# CoproMKII_Ethernet.net
KiCad netlist of a schematic drawn in Altium Designer
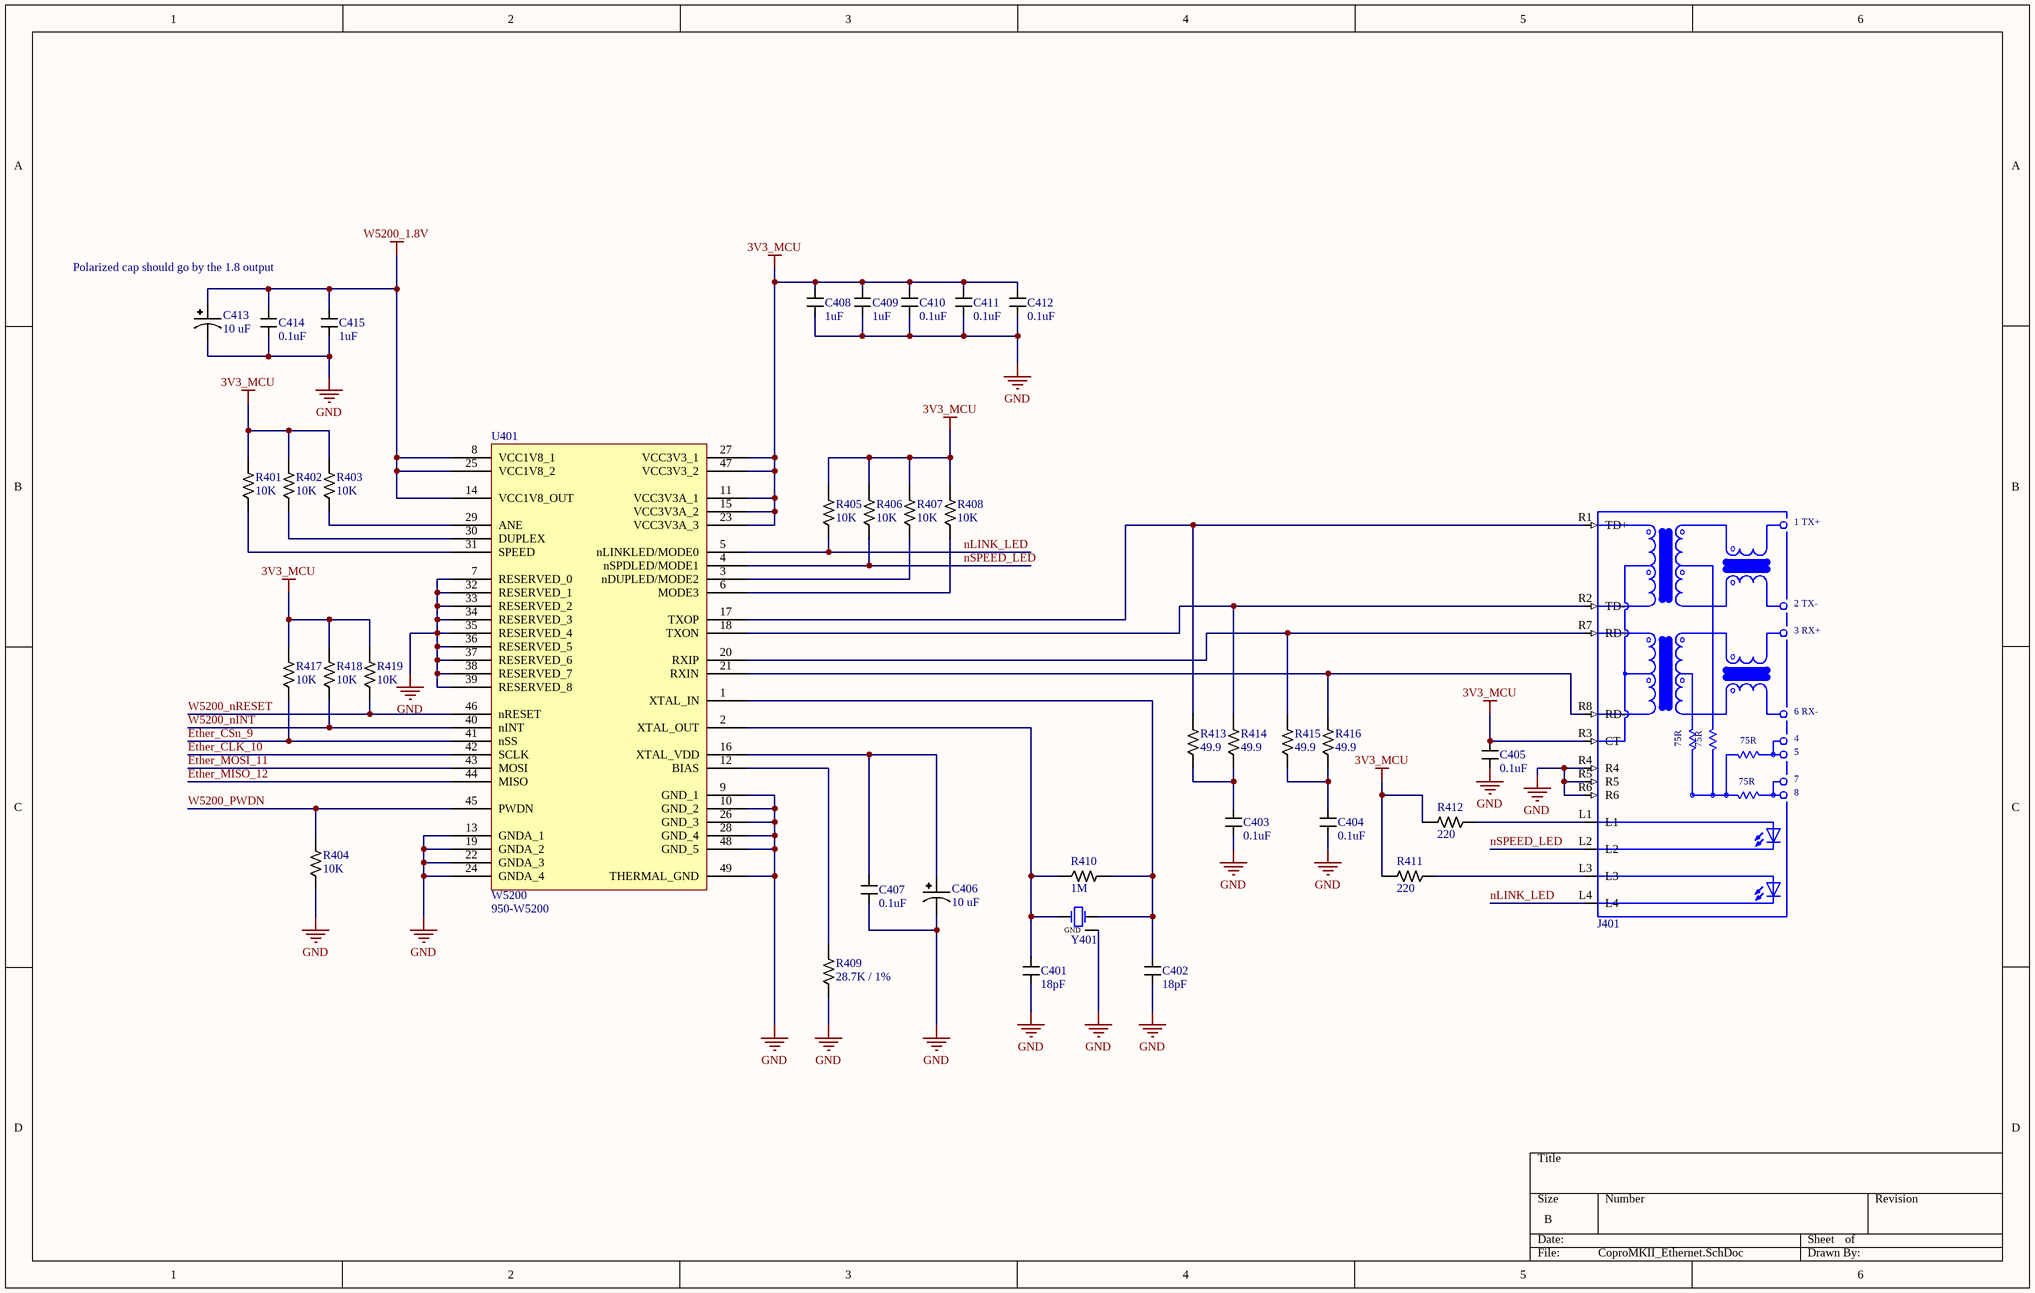
[diagram p0: CoproMKII_Ethernet.SchDoc]

(export (version "E")
  (design (tool "Eeschema 10.0.6"))
  (components
    (comp (ref "C401")
      (value "18pF")
      (footprint "CAPACITOR_0603")
      (description "Cap 18pF 50V +/-5%\r\nCeramic 0603")
      (fields
        (field (name "TOLERANCE") "+/- 5%")
        (field (name "VOLTAGE") "50V")
        (field (name "MADE BY") "Flip B")
      )
      (libsource (lib "Capacitors") (part "CAPACITOR_0.000018uF_0603"))
    )
    (comp (ref "C402")
      (value "18pF")
      (footprint "CAPACITOR_0603")
      (description "Cap 18pF 50V +/-5%\r\nCeramic 0603")
      (fields
        (field (name "TOLERANCE") "+/- 5%")
        (field (name "VOLTAGE") "50V")
        (field (name "MADE BY") "Flip B")
      )
      (libsource (lib "Capacitors") (part "CAPACITOR_0.000018uF_0603"))
    )
    (comp (ref "C403")
      (value "0.1uF")
      (footprint "CAPACITOR_0603")
      (description "Cap 100nF 6.3V +/-10%\r\nCeramic 0603")
      (fields
        (field (name "TOLERANCE") "+/- 10%")
        (field (name "VOLTAGE") "6.3V")
        (field (name "MADE BY") "Flip B")
      )
      (libsource (lib "Capacitors") (part "CAPACITOR_0.1uF_0603"))
    )
    (comp (ref "C404")
      (value "0.1uF")
      (footprint "CAPACITOR_0603")
      (description "Cap 100nF 6.3V +/-10%\r\nCeramic 0603")
      (fields
        (field (name "TOLERANCE") "+/- 10%")
        (field (name "VOLTAGE") "6.3V")
        (field (name "MADE BY") "Flip B")
      )
      (libsource (lib "Capacitors") (part "CAPACITOR_0.1uF_0603"))
    )
    (comp (ref "C405")
      (value "0.1uF")
      (footprint "CAPACITOR_0603")
      (description "Cap 100nF 6.3V +/-10%\r\nCeramic 0603")
      (fields
        (field (name "TOLERANCE") "+/- 10%")
        (field (name "VOLTAGE") "6.3V")
        (field (name "MADE BY") "Flip B")
      )
      (libsource (lib "Capacitors") (part "CAPACITOR_0.1uF_0603"))
    )
    (comp (ref "C406")
      (value "10uF Tantalum 10V")
      (footprint "CAPACITOR_0603")
      (description "Cap 10uF 10V +/-20%\r\nTantalum 0603")
      (fields
        (field (name "TOLERANCE") "+/- 20%")
        (field (name "VOLTAGE") "10V")
        (field (name "VALUE (UF)") "10 uF")
        (field (name "MADE BY") "John S")
      )
      (libsource (lib "Capacitors") (part "CAPACITOR_10uF_0603_Tantalum"))
    )
    (comp (ref "C407")
      (value "0.1uF")
      (footprint "CAPACITOR_0603")
      (description "Cap 100nF 6.3V +/-10%\r\nCeramic 0603")
      (fields
        (field (name "TOLERANCE") "+/- 10%")
        (field (name "VOLTAGE") "6.3V")
        (field (name "MADE BY") "Flip B")
      )
      (libsource (lib "Capacitors") (part "CAPACITOR_0.1uF_0603"))
    )
    (comp (ref "C408")
      (value "1uF")
      (footprint "CAPACITOR_0603")
      (description "Cap 1uF 16V +/-10%\r\nCeramic 0603")
      (fields
        (field (name "TOLERANCE") "+/- 10%")
        (field (name "VOLTAGE") "16V")
        (field (name "MADE BY") "Flip B")
      )
      (libsource (lib "Capacitors") (part "CAPACITOR_1uF_0603"))
    )
    (comp (ref "C409")
      (value "1uF")
      (footprint "CAPACITOR_0603")
      (description "Cap 1uF 16V +/-10%\r\nCeramic 0603")
      (fields
        (field (name "TOLERANCE") "+/- 10%")
        (field (name "VOLTAGE") "16V")
        (field (name "MADE BY") "Flip B")
      )
      (libsource (lib "Capacitors") (part "CAPACITOR_1uF_0603"))
    )
    (comp (ref "C410")
      (value "0.1uF")
      (footprint "CAPACITOR_0603")
      (description "Cap 100nF 6.3V +/-10%\r\nCeramic 0603")
      (fields
        (field (name "TOLERANCE") "+/- 10%")
        (field (name "VOLTAGE") "6.3V")
        (field (name "MADE BY") "Flip B")
      )
      (libsource (lib "Capacitors") (part "CAPACITOR_0.1uF_0603"))
    )
    (comp (ref "C411")
      (value "0.1uF")
      (footprint "CAPACITOR_0603")
      (description "Cap 100nF 6.3V +/-10%\r\nCeramic 0603")
      (fields
        (field (name "TOLERANCE") "+/- 10%")
        (field (name "VOLTAGE") "6.3V")
        (field (name "MADE BY") "Flip B")
      )
      (libsource (lib "Capacitors") (part "CAPACITOR_0.1uF_0603"))
    )
    (comp (ref "C412")
      (value "0.1uF")
      (footprint "CAPACITOR_0603")
      (description "Cap 100nF 6.3V +/-10%\r\nCeramic 0603")
      (fields
        (field (name "TOLERANCE") "+/- 10%")
        (field (name "VOLTAGE") "6.3V")
        (field (name "MADE BY") "Flip B")
      )
      (libsource (lib "Capacitors") (part "CAPACITOR_0.1uF_0603"))
    )
    (comp (ref "C413")
      (value "10uF Tantalum 10V")
      (footprint "CAPACITOR_0603")
      (description "Cap 10uF 10V +/-20%\r\nTantalum 0603")
      (fields
        (field (name "TOLERANCE") "+/- 20%")
        (field (name "VOLTAGE") "10V")
        (field (name "VALUE (UF)") "10 uF")
        (field (name "MADE BY") "John S")
      )
      (libsource (lib "Capacitors") (part "CAPACITOR_10uF_0603_Tantalum"))
    )
    (comp (ref "C414")
      (value "0.1uF")
      (footprint "CAPACITOR_0603")
      (description "Cap 100nF 6.3V +/-10%\r\nCeramic 0603")
      (fields
        (field (name "TOLERANCE") "+/- 10%")
        (field (name "VOLTAGE") "6.3V")
        (field (name "MADE BY") "Flip B")
      )
      (libsource (lib "Capacitors") (part "CAPACITOR_0.1uF_0603"))
    )
    (comp (ref "C415")
      (value "1uF")
      (footprint "CAPACITOR_0603")
      (description "Cap 1uF 16V +/-10%\r\nCeramic 0603")
      (fields
        (field (name "TOLERANCE") "+/- 10%")
        (field (name "VOLTAGE") "16V")
        (field (name "MADE BY") "Flip B")
      )
      (libsource (lib "Capacitors") (part "CAPACITOR_1uF_0603"))
    )
    (comp (ref "J401")
      (value "Ethernet Connector")
      (footprint "WIZNET_RB1-125BAG1A")
      (description "CONN JACK 1PORT 100 BASE-T PCB")
      (libsource (lib "Connectors") (part "RB1-125BAG1A"))
    )
    (comp (ref "R401")
      (value "10k Ohm 5% 1/10W")
      (footprint "RESISTOR_0603")
      (description "RES 10k OHM 5% 1/10W 0603")
      (fields
        (field (name "TOLERANCE") "+/- 5%")
        (field (name "VALUE  (OHMS)") "10K")
        (field (name "MADE BY") "Robert Pafford")
      )
      (libsource (lib "Resistors") (part "RESISTOR_10K_0603"))
    )
    (comp (ref "R402")
      (value "10k Ohm 5% 1/10W")
      (footprint "RESISTOR_0603")
      (description "RES 10k OHM 5% 1/10W 0603")
      (fields
        (field (name "TOLERANCE") "+/- 5%")
        (field (name "VALUE  (OHMS)") "10K")
        (field (name "MADE BY") "Robert Pafford")
      )
      (libsource (lib "Resistors") (part "RESISTOR_10K_0603"))
    )
    (comp (ref "R403")
      (value "10k Ohm 5% 1/10W")
      (footprint "RESISTOR_0603")
      (description "RES 10k OHM 5% 1/10W 0603")
      (fields
        (field (name "TOLERANCE") "+/- 5%")
        (field (name "VALUE  (OHMS)") "10K")
        (field (name "MADE BY") "Robert Pafford")
      )
      (libsource (lib "Resistors") (part "RESISTOR_10K_0603"))
    )
    (comp (ref "R404")
      (value "10k Ohm 5% 1/10W")
      (footprint "RESISTOR_0603")
      (description "RES 10k OHM 5% 1/10W 0603")
      (fields
        (field (name "TOLERANCE") "+/- 5%")
        (field (name "VALUE  (OHMS)") "10K")
        (field (name "MADE BY") "Robert Pafford")
      )
      (libsource (lib "Resistors") (part "RESISTOR_10K_0603"))
    )
    (comp (ref "R405")
      (value "10k Ohm 5% 1/10W")
      (footprint "RESISTOR_0603")
      (description "RES 10k OHM 5% 1/10W 0603")
      (fields
        (field (name "TOLERANCE") "+/- 5%")
        (field (name "VALUE  (OHMS)") "10K")
        (field (name "MADE BY") "Robert Pafford")
      )
      (libsource (lib "Resistors") (part "RESISTOR_10K_0603"))
    )
    (comp (ref "R406")
      (value "10k Ohm 5% 1/10W")
      (footprint "RESISTOR_0603")
      (description "RES 10k OHM 5% 1/10W 0603")
      (fields
        (field (name "TOLERANCE") "+/- 5%")
        (field (name "VALUE  (OHMS)") "10K")
        (field (name "MADE BY") "Robert Pafford")
      )
      (libsource (lib "Resistors") (part "RESISTOR_10K_0603"))
    )
    (comp (ref "R407")
      (value "10k Ohm 5% 1/10W")
      (footprint "RESISTOR_0603")
      (description "RES 10k OHM 5% 1/10W 0603")
      (fields
        (field (name "TOLERANCE") "+/- 5%")
        (field (name "VALUE  (OHMS)") "10K")
        (field (name "MADE BY") "Robert Pafford")
      )
      (libsource (lib "Resistors") (part "RESISTOR_10K_0603"))
    )
    (comp (ref "R408")
      (value "10k Ohm 5% 1/10W")
      (footprint "RESISTOR_0603")
      (description "RES 10k OHM 5% 1/10W 0603")
      (fields
        (field (name "TOLERANCE") "+/- 5%")
        (field (name "VALUE  (OHMS)") "10K")
        (field (name "MADE BY") "Robert Pafford")
      )
      (libsource (lib "Resistors") (part "RESISTOR_10K_0603"))
    )
    (comp (ref "R409")
      (value "K / 1%")
      (footprint "RESISTOR_0603")
      (description "RES 28.7K OHM 1% 1/8W 0603")
      (fields
        (field (name "TOLERANCE") "+/- 5%")
        (field (name "VALUE  (OHMS)") "28.7K / 1%")
        (field (name "MADE BY") "Robert Pafford")
      )
      (libsource (lib "Resistors") (part "RESISTOR_28.7K / 1%_0603"))
    )
    (comp (ref "R410")
      (value "1M")
      (footprint "RESISTOR_0603")
      (description "RES 1M OHM 1/8W 0603")
      (fields
        (field (name "TOLERANCE") "+/- 5%")
        (field (name "VALUE  (OHMS)") "1M")
        (field (name "MADE BY") "Robert Pafford")
      )
      (libsource (lib "Resistors") (part "RESISTOR_1M_0603"))
    )
    (comp (ref "R411")
      (value "220 Ohm 5% 1/8W")
      (footprint "RESISTOR_0603")
      (description "RES 220 OHM 5% 1/8W 0603")
      (fields
        (field (name "TOLERANCE") "+/- 5%")
        (field (name "VALUE  (OHMS)") "220")
        (field (name "MADE BY") "John S")
      )
      (libsource (lib "Resistors") (part "RESISTOR_200_0603"))
    )
    (comp (ref "R412")
      (value "220 Ohm 5% 1/8W")
      (footprint "RESISTOR_0603")
      (description "RES 220 OHM 5% 1/8W 0603")
      (fields
        (field (name "TOLERANCE") "+/- 5%")
        (field (name "VALUE  (OHMS)") "220")
        (field (name "MADE BY") "John S")
      )
      (libsource (lib "Resistors") (part "RESISTOR_200_0603"))
    )
    (comp (ref "R413")
      (value "49.9 Ohm 1% 1/8W")
      (footprint "RESISTOR_0603")
      (description "RES 49.9 OHM 1% 1/8W 0603")
      (fields
        (field (name "TOLERANCE") "+/- 1%")
        (field (name "VALUE  (OHMS)") "49.9")
        (field (name "MADE BY") "John S")
      )
      (libsource (lib "Resistors") (part "RESISTOR_49.9_0603"))
    )
    (comp (ref "R414")
      (value "49.9 Ohm 1% 1/8W")
      (footprint "RESISTOR_0603")
      (description "RES 49.9 OHM 1% 1/8W 0603")
      (fields
        (field (name "TOLERANCE") "+/- 1%")
        (field (name "VALUE  (OHMS)") "49.9")
        (field (name "MADE BY") "John S")
      )
      (libsource (lib "Resistors") (part "RESISTOR_49.9_0603"))
    )
    (comp (ref "R415")
      (value "49.9 Ohm 1% 1/8W")
      (footprint "RESISTOR_0603")
      (description "RES 49.9 OHM 1% 1/8W 0603")
      (fields
        (field (name "TOLERANCE") "+/- 1%")
        (field (name "VALUE  (OHMS)") "49.9")
        (field (name "MADE BY") "John S")
      )
      (libsource (lib "Resistors") (part "RESISTOR_49.9_0603"))
    )
    (comp (ref "R416")
      (value "49.9 Ohm 1% 1/8W")
      (footprint "RESISTOR_0603")
      (description "RES 49.9 OHM 1% 1/8W 0603")
      (fields
        (field (name "TOLERANCE") "+/- 1%")
        (field (name "VALUE  (OHMS)") "49.9")
        (field (name "MADE BY") "John S")
      )
      (libsource (lib "Resistors") (part "RESISTOR_49.9_0603"))
    )
    (comp (ref "R417")
      (value "10k Ohm 5% 1/10W")
      (footprint "RESISTOR_0603")
      (description "RES 10k OHM 5% 1/10W 0603")
      (fields
        (field (name "TOLERANCE") "+/- 5%")
        (field (name "VALUE  (OHMS)") "10K")
        (field (name "MADE BY") "Robert Pafford")
      )
      (libsource (lib "Resistors") (part "RESISTOR_10K_0603"))
    )
    (comp (ref "R418")
      (value "10k Ohm 5% 1/10W")
      (footprint "RESISTOR_0603")
      (description "RES 10k OHM 5% 1/10W 0603")
      (fields
        (field (name "TOLERANCE") "+/- 5%")
        (field (name "VALUE  (OHMS)") "10K")
        (field (name "MADE BY") "Robert Pafford")
      )
      (libsource (lib "Resistors") (part "RESISTOR_10K_0603"))
    )
    (comp (ref "R419")
      (value "10k Ohm 5% 1/10W")
      (footprint "RESISTOR_0603")
      (description "RES 10k OHM 5% 1/10W 0603")
      (fields
        (field (name "TOLERANCE") "+/- 5%")
        (field (name "VALUE  (OHMS)") "10K")
        (field (name "MADE BY") "Robert Pafford")
      )
      (libsource (lib "Resistors") (part "RESISTOR_10K_0603"))
    )
    (comp (ref "U401")
      (value "W5200")
      (footprint "QFN-48")
      (description "WIZNET W5200\r\n48QFN (7x7 mm)")
      (fields
        (field (name "MF") "Texas Instruments")
        (field (name "MP") "LM1117IMPX-3.3/NOPB")
        (field (name "SUPPLIER PART NUMBER 1") "950-W5200")
        (field (name "CREATED BY:") "Siddharth.V")
      )
      (libsource (lib "Integrated Circuits") (part "W5200"))
    )
    (comp (ref "Y401")
      (value "CRYSTAL 12.0000MHZ 18PF SMD")
      (footprint "4-SMD No Lead Crystal")
      (description "25 MHz ±20ppm Crystal 18pF")
      (fields (field (name "MADE BY") "Robert Pafford"))
      (libsource (lib "Crystals") (part "CRYSTAL_25MHz_SMD_1"))
    )
  )
  (nets
    (net (code "1") (name "/Ether_CLK_10") (class "Default")
      (node (ref "U401") (pin "42") (pinfunction "SCLK_42") (pintype "passive"))
    )
    (net (code "2") (name "/Ether_CSn_9") (class "Default")
      (node (ref "R417") (pin "2") (pinfunction "2_2") (pintype "passive"))
      (node (ref "U401") (pin "41") (pinfunction "nSS_41") (pintype "passive"))
    )
    (net (code "3") (name "/Ether_MISO_12") (class "Default")
      (node (ref "U401") (pin "44") (pinfunction "MISO_44") (pintype "passive"))
    )
    (net (code "4") (name "/Ether_MOSI_11") (class "Default")
      (node (ref "U401") (pin "43") (pinfunction "MOSI_43") (pintype "passive"))
    )
    (net (code "5") (name "/W5200_PWDN") (class "Default")
      (node (ref "R404") (pin "1") (pinfunction "1_1") (pintype "passive"))
      (node (ref "U401") (pin "45") (pinfunction "PWDN_45") (pintype "passive"))
    )
    (net (code "6") (name "/W5200_nINT") (class "Default")
      (node (ref "R418") (pin "2") (pinfunction "2_2") (pintype "passive"))
      (node (ref "U401") (pin "40") (pinfunction "nINT_40") (pintype "passive"))
    )
    (net (code "7") (name "/W5200_nRESET") (class "Default")
      (node (ref "R419") (pin "2") (pinfunction "2_2") (pintype "passive"))
      (node (ref "U401") (pin "46") (pinfunction "nRESET_46") (pintype "passive"))
    )
    (net (code "8") (name "/nLINK_LED") (class "Default")
      (node (ref "J401") (pin "L4") (pinfunction "L4_L4") (pintype "passive"))
      (node (ref "R405") (pin "2") (pinfunction "2_2") (pintype "passive"))
      (node (ref "U401") (pin "5") (pinfunction "nLINKLED/MODE0_5") (pintype "passive"))
    )
    (net (code "9") (name "/nSPEED_LED") (class "Default")
      (node (ref "J401") (pin "L2") (pinfunction "L2_L2") (pintype "passive"))
      (node (ref "R406") (pin "2") (pinfunction "2_2") (pintype "passive"))
      (node (ref "U401") (pin "4") (pinfunction "nSPDLED/MODE1_4") (pintype "passive"))
    )
    (net (code "10") (name "3V3_MCU") (class "Default")
      (node (ref "C405") (pin "1") (pinfunction "1_1") (pintype "passive"))
      (node (ref "C408") (pin "1") (pinfunction "1_1") (pintype "passive"))
      (node (ref "C409") (pin "1") (pinfunction "1_1") (pintype "passive"))
      (node (ref "C410") (pin "1") (pinfunction "1_1") (pintype "passive"))
      (node (ref "C411") (pin "1") (pinfunction "1_1") (pintype "passive"))
      (node (ref "C412") (pin "1") (pinfunction "1_1") (pintype "passive"))
      (node (ref "J401") (pin "R3") (pinfunction "CT_R3") (pintype "input"))
      (node (ref "R401") (pin "1") (pinfunction "1_1") (pintype "passive"))
      (node (ref "R402") (pin "1") (pinfunction "1_1") (pintype "passive"))
      (node (ref "R403") (pin "1") (pinfunction "1_1") (pintype "passive"))
      (node (ref "R405") (pin "1") (pinfunction "1_1") (pintype "passive"))
      (node (ref "R406") (pin "1") (pinfunction "1_1") (pintype "passive"))
      (node (ref "R407") (pin "1") (pinfunction "1_1") (pintype "passive"))
      (node (ref "R408") (pin "1") (pinfunction "1_1") (pintype "passive"))
      (node (ref "R411") (pin "1") (pinfunction "1_1") (pintype "passive"))
      (node (ref "R412") (pin "1") (pinfunction "1_1") (pintype "passive"))
      (node (ref "R417") (pin "1") (pinfunction "1_1") (pintype "passive"))
      (node (ref "R418") (pin "1") (pinfunction "1_1") (pintype "passive"))
      (node (ref "R419") (pin "1") (pinfunction "1_1") (pintype "passive"))
      (node (ref "U401") (pin "11") (pinfunction "VCC3V3A_1_11") (pintype "passive"))
      (node (ref "U401") (pin "15") (pinfunction "VCC3V3A_2_15") (pintype "passive"))
      (node (ref "U401") (pin "23") (pinfunction "VCC3V3A_3_23") (pintype "passive"))
      (node (ref "U401") (pin "27") (pinfunction "VCC3V3_1_27") (pintype "passive"))
      (node (ref "U401") (pin "47") (pinfunction "VCC3V3_2_47") (pintype "passive"))
    )
    (net (code "11") (name "GND") (class "Default")
      (node (ref "C401") (pin "2") (pinfunction "2_2") (pintype "passive"))
      (node (ref "C402") (pin "2") (pinfunction "2_2") (pintype "passive"))
      (node (ref "C403") (pin "2") (pinfunction "2_2") (pintype "passive"))
      (node (ref "C404") (pin "2") (pinfunction "2_2") (pintype "passive"))
      (node (ref "C405") (pin "2") (pinfunction "2_2") (pintype "passive"))
      (node (ref "C406") (pin "2") (pintype "passive"))
      (node (ref "C407") (pin "2") (pinfunction "2_2") (pintype "passive"))
      (node (ref "C408") (pin "2") (pinfunction "2_2") (pintype "passive"))
      (node (ref "C409") (pin "2") (pinfunction "2_2") (pintype "passive"))
      (node (ref "C410") (pin "2") (pinfunction "2_2") (pintype "passive"))
      (node (ref "C411") (pin "2") (pinfunction "2_2") (pintype "passive"))
      (node (ref "C412") (pin "2") (pinfunction "2_2") (pintype "passive"))
      (node (ref "C413") (pin "2") (pintype "passive"))
      (node (ref "C414") (pin "2") (pinfunction "2_2") (pintype "passive"))
      (node (ref "C415") (pin "2") (pinfunction "2_2") (pintype "passive"))
      (node (ref "J401") (pin "R4") (pinfunction "R4_R4") (pintype "input"))
      (node (ref "J401") (pin "R5") (pinfunction "R5_R5") (pintype "input"))
      (node (ref "J401") (pin "R6") (pinfunction "R6_R6") (pintype "input"))
      (node (ref "R404") (pin "2") (pinfunction "2_2") (pintype "passive"))
      (node (ref "R409") (pin "2") (pinfunction "2_2") (pintype "passive"))
      (node (ref "U401") (pin "10") (pinfunction "GND_2_10") (pintype "passive"))
      (node (ref "U401") (pin "13") (pinfunction "GNDA_1_13") (pintype "passive"))
      (node (ref "U401") (pin "19") (pinfunction "GNDA_2_19") (pintype "passive"))
      (node (ref "U401") (pin "22") (pinfunction "GNDA_3_22") (pintype "passive"))
      (node (ref "U401") (pin "24") (pinfunction "GNDA_4_24") (pintype "passive"))
      (node (ref "U401") (pin "26") (pinfunction "GND_3_26") (pintype "passive"))
      (node (ref "U401") (pin "28") (pinfunction "GND_4_28") (pintype "passive"))
      (node (ref "U401") (pin "32") (pinfunction "RESERVED_1_32") (pintype "passive"))
      (node (ref "U401") (pin "33") (pinfunction "RESERVED_2_33") (pintype "passive"))
      (node (ref "U401") (pin "34") (pinfunction "RESERVED_3_34") (pintype "passive"))
      (node (ref "U401") (pin "35") (pinfunction "RESERVED_4_35") (pintype "passive"))
      (node (ref "U401") (pin "36") (pinfunction "RESERVED_5_36") (pintype "passive"))
      (node (ref "U401") (pin "37") (pinfunction "RESERVED_6_37") (pintype "passive"))
      (node (ref "U401") (pin "38") (pinfunction "RESERVED_7_38") (pintype "passive"))
      (node (ref "U401") (pin "39") (pinfunction "RESERVED_8_39") (pintype "passive"))
      (node (ref "U401") (pin "48") (pinfunction "GND_5_48") (pintype "passive"))
      (node (ref "U401") (pin "49") (pinfunction "THERMAL_GND_49") (pintype "passive"))
      (node (ref "U401") (pin "7") (pinfunction "RESERVED_0_7") (pintype "passive"))
      (node (ref "U401") (pin "9") (pinfunction "GND_1_9") (pintype "passive"))
      (node (ref "Y401") (pin "GND") (pinfunction "GND_GND") (pintype "power_in"))
    )
    (net (code "12") (name "Net-(C403-Pad1)") (class "Default")
      (node (ref "C403") (pin "1") (pinfunction "1_1") (pintype "passive"))
      (node (ref "R413") (pin "2") (pinfunction "2_2") (pintype "passive"))
      (node (ref "R414") (pin "2") (pinfunction "2_2") (pintype "passive"))
    )
    (net (code "13") (name "Net-(C404-Pad1)") (class "Default")
      (node (ref "C404") (pin "1") (pinfunction "1_1") (pintype "passive"))
      (node (ref "R415") (pin "2") (pinfunction "2_2") (pintype "passive"))
      (node (ref "R416") (pin "2") (pinfunction "2_2") (pintype "passive"))
    )
    (net (code "14") (name "Net-(J401-PadL1)") (class "Default")
      (node (ref "J401") (pin "L1") (pinfunction "L1_L1") (pintype "passive"))
      (node (ref "R412") (pin "2") (pinfunction "2_2") (pintype "passive"))
    )
    (net (code "15") (name "Net-(J401-PadL3)") (class "Default")
      (node (ref "J401") (pin "L3") (pinfunction "L3_L3") (pintype "passive"))
      (node (ref "R411") (pin "2") (pinfunction "2_2") (pintype "passive"))
    )
    (net (code "16") (name "Net-(J401-RD+)") (class "Default")
      (node (ref "J401") (pin "R7") (pinfunction "RD+_R7") (pintype "input"))
      (node (ref "R415") (pin "1") (pinfunction "1_1") (pintype "passive"))
      (node (ref "U401") (pin "20") (pinfunction "RXIP_20") (pintype "passive"))
    )
    (net (code "17") (name "Net-(J401-RD-)") (class "Default")
      (node (ref "J401") (pin "R8") (pinfunction "RD-_R8") (pintype "input"))
      (node (ref "R416") (pin "1") (pinfunction "1_1") (pintype "passive"))
      (node (ref "U401") (pin "21") (pinfunction "RXIN_21") (pintype "passive"))
    )
    (net (code "18") (name "Net-(J401-TD+)") (class "Default")
      (node (ref "J401") (pin "R1") (pinfunction "TD+_R1") (pintype "input"))
      (node (ref "R413") (pin "1") (pinfunction "1_1") (pintype "passive"))
      (node (ref "U401") (pin "17") (pinfunction "TXOP_17") (pintype "passive"))
    )
    (net (code "19") (name "Net-(J401-TD-)") (class "Default")
      (node (ref "J401") (pin "R2") (pinfunction "TD-_R2") (pintype "input"))
      (node (ref "R414") (pin "1") (pinfunction "1_1") (pintype "passive"))
      (node (ref "U401") (pin "18") (pinfunction "TXON_18") (pintype "passive"))
    )
    (net (code "20") (name "Net-(U401-ANE)") (class "Default")
      (node (ref "R403") (pin "2") (pinfunction "2_2") (pintype "passive"))
      (node (ref "U401") (pin "29") (pinfunction "ANE_29") (pintype "passive"))
    )
    (net (code "21") (name "Net-(U401-BIAS)") (class "Default")
      (node (ref "R409") (pin "1") (pinfunction "1_1") (pintype "passive"))
      (node (ref "U401") (pin "12") (pinfunction "BIAS_12") (pintype "passive"))
    )
    (net (code "22") (name "Net-(U401-DUPLEX)") (class "Default")
      (node (ref "R402") (pin "2") (pinfunction "2_2") (pintype "passive"))
      (node (ref "U401") (pin "30") (pinfunction "DUPLEX_30") (pintype "passive"))
    )
    (net (code "23") (name "Net-(U401-MODE3)") (class "Default")
      (node (ref "R408") (pin "2") (pinfunction "2_2") (pintype "passive"))
      (node (ref "U401") (pin "6") (pinfunction "MODE3_6") (pintype "passive"))
    )
    (net (code "24") (name "Net-(U401-SPEED)") (class "Default")
      (node (ref "R401") (pin "2") (pinfunction "2_2") (pintype "passive"))
      (node (ref "U401") (pin "31") (pinfunction "SPEED_31") (pintype "passive"))
    )
    (net (code "25") (name "Net-(U401-XTAL_IN)") (class "Default")
      (node (ref "C402") (pin "1") (pinfunction "1_1") (pintype "passive"))
      (node (ref "R410") (pin "1") (pinfunction "1_1") (pintype "passive"))
      (node (ref "U401") (pin "1") (pinfunction "XTAL_IN_1") (pintype "passive"))
      (node (ref "Y401") (pin "2") (pinfunction "2_2") (pintype "passive"))
    )
    (net (code "26") (name "Net-(U401-XTAL_OUT)") (class "Default")
      (node (ref "C401") (pin "1") (pinfunction "1_1") (pintype "passive"))
      (node (ref "R410") (pin "2") (pinfunction "2_2") (pintype "passive"))
      (node (ref "U401") (pin "2") (pinfunction "XTAL_OUT_2") (pintype "passive"))
      (node (ref "Y401") (pin "1") (pinfunction "1_1") (pintype "passive"))
    )
    (net (code "27") (name "Net-(U401-XTAL_VDD)") (class "Default")
      (node (ref "C406") (pin "1") (pintype "passive"))
      (node (ref "C407") (pin "1") (pinfunction "1_1") (pintype "passive"))
      (node (ref "U401") (pin "16") (pinfunction "XTAL_VDD_16") (pintype "passive"))
    )
    (net (code "28") (name "Net-(U401-nDUPLED{slash}MODE2)") (class "Default")
      (node (ref "R407") (pin "2") (pinfunction "2_2") (pintype "passive"))
      (node (ref "U401") (pin "3") (pinfunction "nDUPLED/MODE2_3") (pintype "passive"))
    )
    (net (code "29") (name "W5200_1.8V") (class "Default")
      (node (ref "C413") (pin "1") (pintype "passive"))
      (node (ref "C414") (pin "1") (pinfunction "1_1") (pintype "passive"))
      (node (ref "C415") (pin "1") (pinfunction "1_1") (pintype "passive"))
      (node (ref "U401") (pin "14") (pinfunction "VCC1V8_OUT_14") (pintype "passive"))
      (node (ref "U401") (pin "25") (pinfunction "VCC1V8_2_25") (pintype "passive"))
      (node (ref "U401") (pin "8") (pinfunction "VCC1V8_1_8") (pintype "passive"))
    )
  )
)
